# SpeechSynthesisBoard.net
KiCad netlist of a schematic drawn in EAGLE
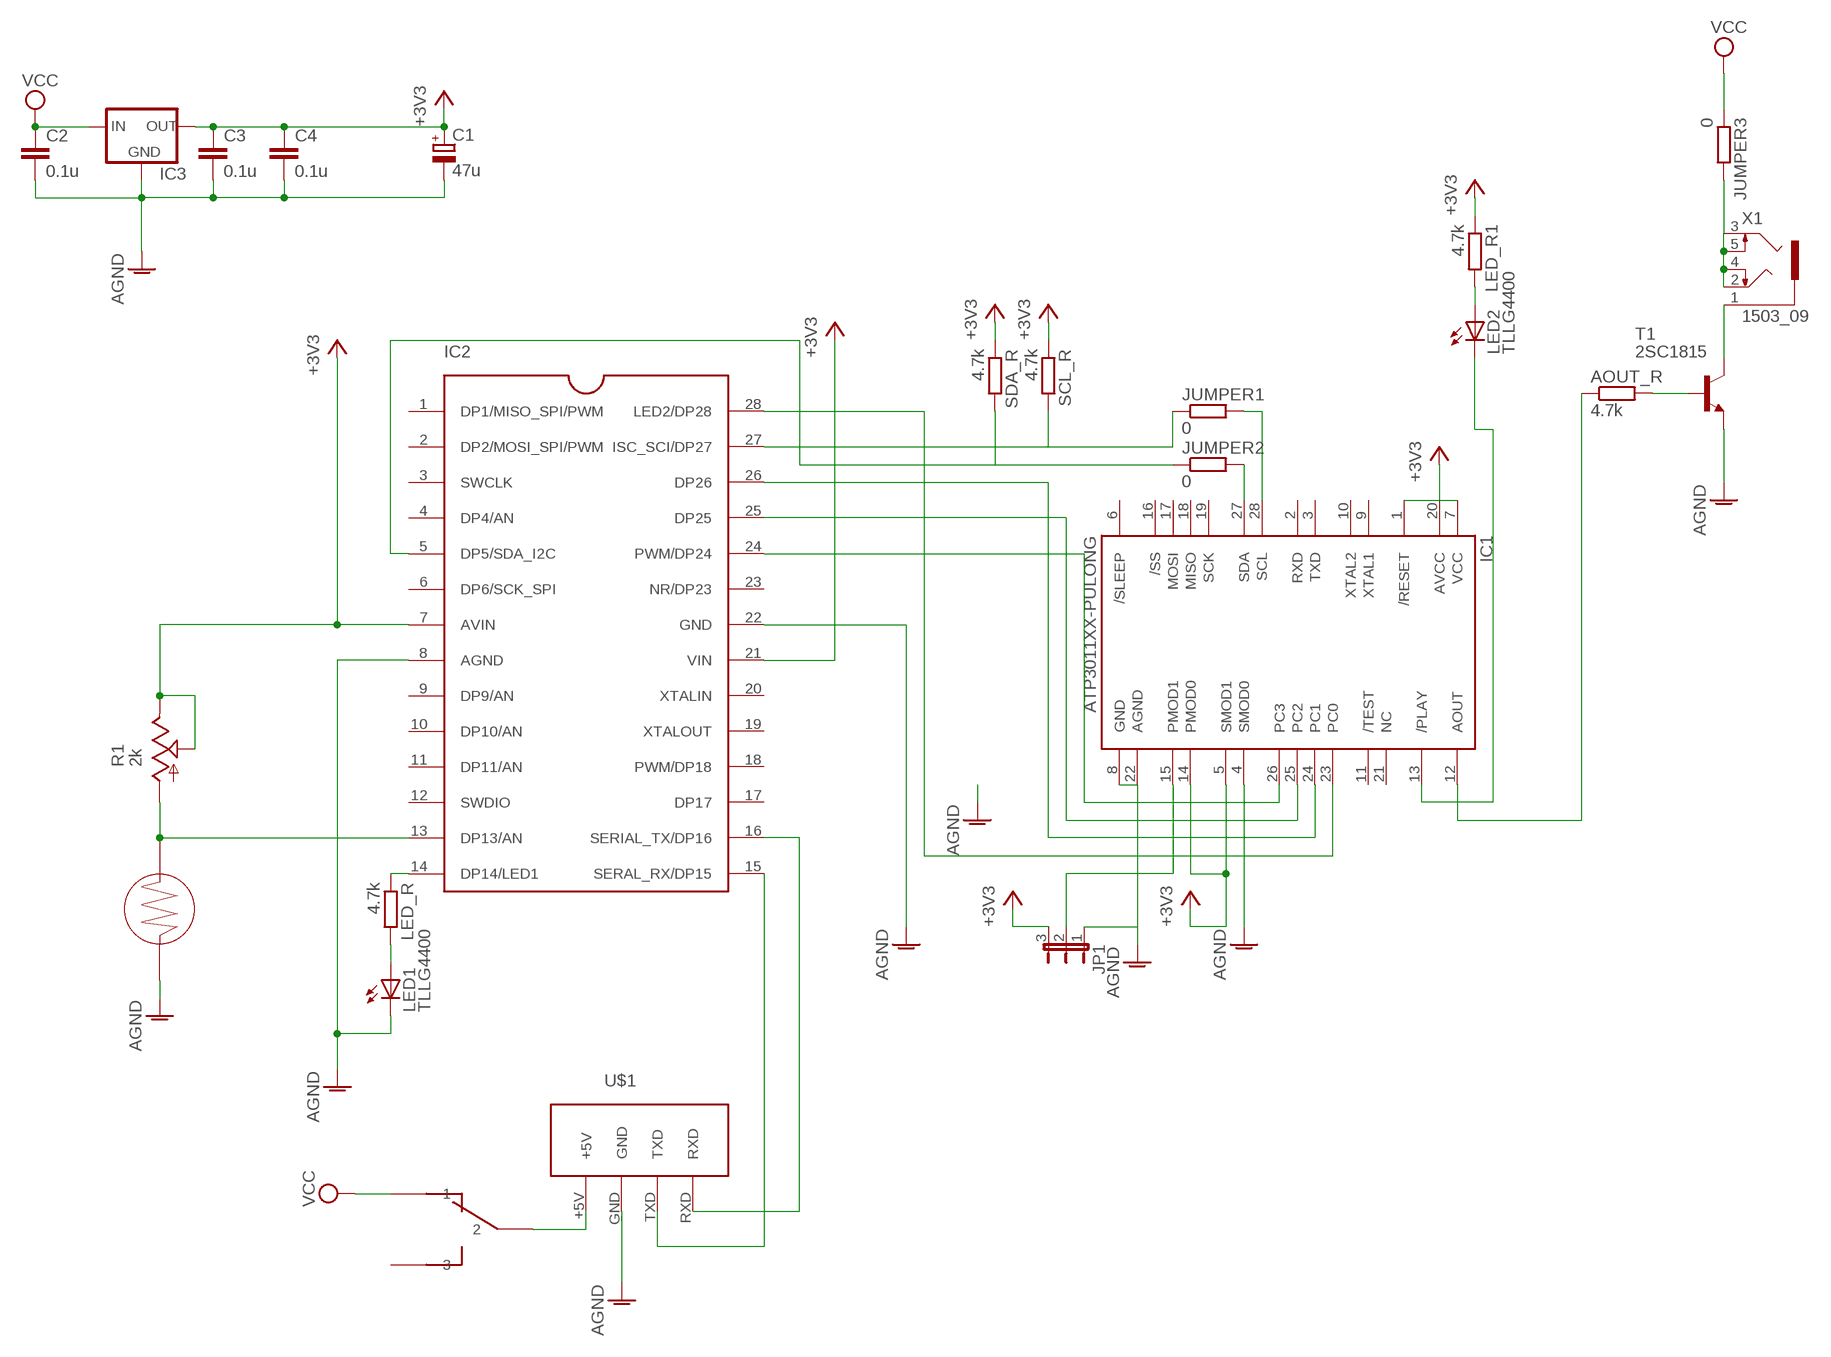
[diagram p0: schematic, sheet 1]

(export (version "E")
  (design (tool "Eeschema 10.0.6"))
  (components
    (comp (ref "AOUT_R")
      (value "4.7k")
      (footprint "eagle-import:0204_7")
      (libsource (lib "eagle-import") (part "R-EU_0204/7"))
    )
    (comp (ref "B-12JB1")
      (value "B-12JV")
      (footprint "eagle-import:B-12JV")
      (libsource (lib "eagle-import") (part "B-12JV"))
    )
    (comp (ref "C1")
      (value "47u")
      (footprint "eagle-import:E2,5-5")
      (libsource (lib "eagle-import") (part "CPOL-EUE2.5-5"))
    )
    (comp (ref "C2")
      (value "0.1u")
      (footprint "eagle-import:C025-024X044")
      (libsource (lib "eagle-import") (part "C-EU025-024X044"))
    )
    (comp (ref "C3")
      (value "0.1u")
      (footprint "eagle-import:C025-024X044")
      (libsource (lib "eagle-import") (part "C-EU025-024X044"))
    )
    (comp (ref "C4")
      (value "0.1u")
      (footprint "eagle-import:C025-024X044")
      (libsource (lib "eagle-import") (part "C-EU025-024X044"))
    )
    (comp (ref "CDS_5MM1")
      (value "CDS_5MM")
      (footprint "eagle-import:CDS_5MM")
      (libsource (lib "eagle-import") (part "CDS_5MM"))
    )
    (comp (ref "IC1")
      (value "ATP3011XX-PULONG")
      (footprint "eagle-import:DIL28-3")
      (libsource (lib "eagle-import") (part "ATP3011XX-PULONG"))
    )
    (comp (ref "IC2")
      (value "LPC1114FN28")
      (footprint "eagle-import:DIP28")
      (libsource (lib "eagle-import") (part "LPC1114FN28"))
    )
    (comp (ref "IC3")
      (value "78XXL")
      (footprint "eagle-import:78XXL")
      (libsource (lib "eagle-import") (part "78XXL"))
    )
    (comp (ref "JP1")
      (value "JP2E")
      (footprint "eagle-import:JP2")
      (libsource (lib "eagle-import") (part "JP2E"))
    )
    (comp (ref "JUMPER1")
      (value "0")
      (footprint "eagle-import:0309_12")
      (libsource (lib "eagle-import") (part "R-EU_0309/12"))
    )
    (comp (ref "JUMPER2")
      (value "0")
      (footprint "eagle-import:0309_12")
      (libsource (lib "eagle-import") (part "R-EU_0309/12"))
    )
    (comp (ref "JUMPER3")
      (value "0")
      (footprint "eagle-import:0309_12")
      (libsource (lib "eagle-import") (part "R-EU_0309/12"))
    )
    (comp (ref "LED1")
      (value "TLLG4400")
      (footprint "eagle-import:LED3MM")
      (fields (field (name "MF") "VISHAY SEMICONDUCTOR"))
      (libsource (lib "eagle-import") (part "TLLG4400"))
    )
    (comp (ref "LED2")
      (value "TLLG4400")
      (footprint "eagle-import:LED3MM")
      (fields (field (name "MF") "VISHAY SEMICONDUCTOR"))
      (libsource (lib "eagle-import") (part "TLLG4400"))
    )
    (comp (ref "LED_R")
      (value "4.7k")
      (footprint "eagle-import:0204_7")
      (libsource (lib "eagle-import") (part "R-EU_0204/7"))
    )
    (comp (ref "LED_R1")
      (value "4.7k")
      (footprint "eagle-import:0204_7")
      (libsource (lib "eagle-import") (part "R-EU_0204/7"))
    )
    (comp (ref "R1")
      (value "2k")
      (footprint "eagle-import:CA6V")
      (libsource (lib "eagle-import") (part "TRIM_US-CA6V"))
    )
    (comp (ref "SCL_R")
      (value "4.7k")
      (footprint "eagle-import:0204_7")
      (libsource (lib "eagle-import") (part "R-EU_0204/7"))
    )
    (comp (ref "SDA_R")
      (value "4.7k")
      (footprint "eagle-import:0204_7")
      (libsource (lib "eagle-import") (part "R-EU_0204/7"))
    )
    (comp (ref "T1")
      (value "2SC1815")
      (footprint "eagle-import:TO92-ECB")
      (libsource (lib "eagle-import") (part "2SC1815"))
    )
    (comp (ref "U$1")
      (value "USB2UART")
      (footprint "eagle-import:USB2UART")
      (libsource (lib "eagle-import") (part "USB2UART"))
    )
    (comp (ref "X1")
      (value "1503_09")
      (footprint "eagle-import:1503_09")
      (libsource (lib "eagle-import") (part "1503_09"))
    )
  )
  (nets
    (net (code "1") (name "+3V3") (class "Default")
      (node (ref "C1") (pin "+") (pinfunction "+_+") (pintype "passive"))
      (node (ref "C3") (pin "1") (pinfunction "1_1") (pintype "passive"))
      (node (ref "C4") (pin "1") (pinfunction "1_1") (pintype "passive"))
      (node (ref "IC1") (pin "1") (pinfunction "/RESET_1") (pintype "input"))
      (node (ref "IC1") (pin "14") (pinfunction "PMOD0_14") (pintype "input"))
      (node (ref "IC1") (pin "20") (pinfunction "AVCC_20") (pintype "power_in"))
      (node (ref "IC1") (pin "5") (pinfunction "SMOD1_5") (pintype "input"))
      (node (ref "IC1") (pin "7") (pinfunction "VCC_7") (pintype "power_in"))
      (node (ref "IC2") (pin "21") (pinfunction "VIN_21") (pintype "power_in"))
      (node (ref "IC2") (pin "7") (pinfunction "AVIN_7") (pintype "power_in"))
      (node (ref "IC3") (pin "OUT") (pinfunction "OUT_OUT") (pintype "passive"))
      (node (ref "JP1") (pin "3") (pinfunction "3_3") (pintype "passive"))
      (node (ref "LED_R1") (pin "1") (pinfunction "1_1") (pintype "passive"))
      (node (ref "R1") (pin "E") (pinfunction "E_E") (pintype "passive"))
      (node (ref "R1") (pin "S") (pinfunction "S_S") (pintype "passive"))
      (node (ref "SCL_R") (pin "1") (pinfunction "1_1") (pintype "passive"))
      (node (ref "SDA_R") (pin "1") (pinfunction "1_1") (pintype "passive"))
    )
    (net (code "2") (name "AGND") (class "Default")
      (node (ref "C1") (pin "-") (pinfunction "-_-") (pintype "passive"))
      (node (ref "C2") (pin "2") (pinfunction "2_2") (pintype "passive"))
      (node (ref "C3") (pin "2") (pinfunction "2_2") (pintype "passive"))
      (node (ref "C4") (pin "2") (pinfunction "2_2") (pintype "passive"))
      (node (ref "CDS_5MM1") (pin "P$2") (pinfunction "P$2_P$2") (pintype "bidirectional"))
      (node (ref "IC1") (pin "22") (pinfunction "AGND_22") (pintype "power_in"))
      (node (ref "IC1") (pin "4") (pinfunction "SMOD0_4") (pintype "input"))
      (node (ref "IC1") (pin "8") (pinfunction "GND_8") (pintype "power_in"))
      (node (ref "IC2") (pin "22") (pinfunction "GND_22") (pintype "power_in"))
      (node (ref "IC2") (pin "8") (pinfunction "AGND_8") (pintype "power_in"))
      (node (ref "IC3") (pin "GND") (pinfunction "GND_GND") (pintype "input"))
      (node (ref "JP1") (pin "1") (pinfunction "1_1") (pintype "passive"))
      (node (ref "LED1") (pin "K") (pinfunction "C_K") (pintype "passive"))
      (node (ref "T1") (pin "E") (pinfunction "E_E") (pintype "passive"))
      (node (ref "U$1") (pin "GND") (pinfunction "GND_GND") (pintype "bidirectional"))
    )
    (net (code "3") (name "Net-(AOUT_R-Pad2)") (class "Default")
      (node (ref "AOUT_R") (pin "2") (pinfunction "2_2") (pintype "passive"))
      (node (ref "T1") (pin "B") (pinfunction "B_B") (pintype "passive"))
    )
    (net (code "4") (name "Net-(B-12JB1-Pad2)") (class "Default")
      (node (ref "B-12JB1") (pin "2") (pinfunction "2_2") (pintype "bidirectional"))
      (node (ref "U$1") (pin "+5V") (pinfunction "+5V_+5V") (pintype "bidirectional"))
    )
    (net (code "5") (name "Net-(IC1-AOUT)") (class "Default")
      (node (ref "AOUT_R") (pin "1") (pinfunction "1_1") (pintype "passive"))
      (node (ref "IC1") (pin "12") (pinfunction "AOUT_12") (pintype "output"))
    )
    (net (code "6") (name "Net-(IC1-PC0)") (class "Default")
      (node (ref "IC1") (pin "23") (pinfunction "PC0_23") (pintype "input"))
      (node (ref "IC2") (pin "28") (pinfunction "LED2/DP28_28") (pintype "bidirectional"))
    )
    (net (code "7") (name "Net-(IC1-PC1)") (class "Default")
      (node (ref "IC1") (pin "24") (pinfunction "PC1_24") (pintype "input"))
      (node (ref "IC2") (pin "26") (pinfunction "DP26_26") (pintype "bidirectional"))
    )
    (net (code "8") (name "Net-(IC1-PC2)") (class "Default")
      (node (ref "IC1") (pin "25") (pinfunction "PC2_25") (pintype "input"))
      (node (ref "IC2") (pin "25") (pinfunction "DP25_25") (pintype "bidirectional"))
    )
    (net (code "9") (name "Net-(IC1-PC3)") (class "Default")
      (node (ref "IC1") (pin "26") (pinfunction "PC3_26") (pintype "input"))
      (node (ref "IC2") (pin "24") (pinfunction "PWM/DP24_24") (pintype "bidirectional"))
    )
    (net (code "10") (name "Net-(IC1-PMOD1)") (class "Default")
      (node (ref "IC1") (pin "15") (pinfunction "PMOD1_15") (pintype "input"))
      (node (ref "JP1") (pin "2") (pinfunction "2_2") (pintype "passive"))
    )
    (net (code "11") (name "Net-(IC1-SCL)") (class "Default")
      (node (ref "IC1") (pin "28") (pinfunction "SCL_28") (pintype "input"))
      (node (ref "JUMPER1") (pin "2") (pinfunction "2_2") (pintype "passive"))
    )
    (net (code "12") (name "Net-(IC1-SDA)") (class "Default")
      (node (ref "IC1") (pin "27") (pinfunction "SDA_27") (pintype "bidirectional"))
      (node (ref "JUMPER2") (pin "2") (pinfunction "2_2") (pintype "passive"))
    )
    (net (code "13") (name "Net-(IC1-{slash}PLAY)") (class "Default")
      (node (ref "IC1") (pin "13") (pinfunction "/PLAY_13") (pintype "output"))
      (node (ref "LED2") (pin "K") (pinfunction "C_K") (pintype "passive"))
    )
    (net (code "14") (name "Net-(IC2-DP5{slash}SDA_I2C)") (class "Default")
      (node (ref "IC2") (pin "5") (pinfunction "DP5/SDA_I2C_5") (pintype "bidirectional"))
      (node (ref "JUMPER2") (pin "1") (pinfunction "1_1") (pintype "passive"))
      (node (ref "SDA_R") (pin "2") (pinfunction "2_2") (pintype "passive"))
    )
    (net (code "15") (name "Net-(IC2-DP13{slash}AN)") (class "Default")
      (node (ref "CDS_5MM1") (pin "P$1") (pinfunction "P$1_P$1") (pintype "bidirectional"))
      (node (ref "IC2") (pin "13") (pinfunction "DP13/AN_13") (pintype "bidirectional"))
      (node (ref "R1") (pin "A") (pinfunction "A_A") (pintype "passive"))
    )
    (net (code "16") (name "Net-(IC2-DP14{slash}LED1)") (class "Default")
      (node (ref "IC2") (pin "14") (pinfunction "DP14/LED1_14") (pintype "bidirectional"))
      (node (ref "LED_R") (pin "1") (pinfunction "1_1") (pintype "passive"))
    )
    (net (code "17") (name "Net-(IC2-ISC_SCI{slash}DP27)") (class "Default")
      (node (ref "IC2") (pin "27") (pinfunction "ISC_SCI/DP27_27") (pintype "bidirectional"))
      (node (ref "JUMPER1") (pin "1") (pinfunction "1_1") (pintype "passive"))
      (node (ref "SCL_R") (pin "2") (pinfunction "2_2") (pintype "passive"))
    )
    (net (code "18") (name "Net-(IC2-SERAL_RX{slash}DP15)") (class "Default")
      (node (ref "IC2") (pin "15") (pinfunction "SERAL_RX/DP15_15") (pintype "bidirectional"))
      (node (ref "U$1") (pin "TXD") (pinfunction "TXD_TXD") (pintype "bidirectional"))
    )
    (net (code "19") (name "Net-(IC2-SERIAL_TX{slash}DP16)") (class "Default")
      (node (ref "IC2") (pin "16") (pinfunction "SERIAL_TX/DP16_16") (pintype "bidirectional"))
      (node (ref "U$1") (pin "RXD") (pinfunction "RXD_RXD") (pintype "bidirectional"))
    )
    (net (code "20") (name "Net-(JUMPER3-Pad2)") (class "Default")
      (node (ref "JUMPER3") (pin "2") (pinfunction "2_2") (pintype "passive"))
      (node (ref "X1") (pin "2") (pinfunction "2_2") (pintype "passive"))
      (node (ref "X1") (pin "3") (pinfunction "3_3") (pintype "passive"))
      (node (ref "X1") (pin "4") (pinfunction "4_4") (pintype "passive"))
      (node (ref "X1") (pin "5") (pinfunction "5_5") (pintype "passive"))
    )
    (net (code "21") (name "Net-(LED1-PadA)") (class "Default")
      (node (ref "LED1") (pin "A") (pinfunction "A_A") (pintype "passive"))
      (node (ref "LED_R") (pin "2") (pinfunction "2_2") (pintype "passive"))
    )
    (net (code "22") (name "Net-(LED2-PadA)") (class "Default")
      (node (ref "LED2") (pin "A") (pinfunction "A_A") (pintype "passive"))
      (node (ref "LED_R1") (pin "2") (pinfunction "2_2") (pintype "passive"))
    )
    (net (code "23") (name "Net-(T1-PadC)") (class "Default")
      (node (ref "T1") (pin "C") (pinfunction "C_C") (pintype "passive"))
      (node (ref "X1") (pin "1") (pinfunction "1_1") (pintype "passive"))
    )
    (net (code "24") (name "VCC") (class "Default")
      (node (ref "B-12JB1") (pin "1") (pinfunction "1_1") (pintype "bidirectional"))
      (node (ref "C2") (pin "1") (pinfunction "1_1") (pintype "passive"))
      (node (ref "IC3") (pin "IN") (pinfunction "IN_IN") (pintype "input"))
      (node (ref "JUMPER3") (pin "1") (pinfunction "1_1") (pintype "passive"))
    )
    (net (code "25") (name "unconnected-(B-12JB1-Pad3)") (class "Default")
      (node (ref "B-12JB1") (pin "3") (pinfunction "3_3") (pintype "bidirectional"))
    )
    (net (code "26") (name "unconnected-(IC1-MISO-Pad18)") (class "Default")
      (node (ref "IC1") (pin "18") (pinfunction "MISO_18") (pintype "output"))
    )
    (net (code "27") (name "unconnected-(IC1-MOSI-Pad17)") (class "Default")
      (node (ref "IC1") (pin "17") (pinfunction "MOSI_17") (pintype "input"))
    )
    (net (code "28") (name "unconnected-(IC1-NC-Pad21)") (class "Default")
      (node (ref "IC1") (pin "21") (pinfunction "NC_21") (pintype "no_connect"))
    )
    (net (code "29") (name "unconnected-(IC1-RXD-Pad2)") (class "Default")
      (node (ref "IC1") (pin "2") (pinfunction "RXD_2") (pintype "input"))
    )
    (net (code "30") (name "unconnected-(IC1-SCK-Pad19)") (class "Default")
      (node (ref "IC1") (pin "19") (pinfunction "SCK_19") (pintype "input"))
    )
    (net (code "31") (name "unconnected-(IC1-TXD-Pad3)") (class "Default")
      (node (ref "IC1") (pin "3") (pinfunction "TXD_3") (pintype "output"))
    )
    (net (code "32") (name "unconnected-(IC1-XTAL1-Pad9)") (class "Default")
      (node (ref "IC1") (pin "9") (pinfunction "XTAL1_9") (pintype "no_connect"))
    )
    (net (code "33") (name "unconnected-(IC1-XTAL2-Pad10)") (class "Default")
      (node (ref "IC1") (pin "10") (pinfunction "XTAL2_10") (pintype "no_connect"))
    )
    (net (code "34") (name "unconnected-(IC1-{slash}SLEEP-Pad6)") (class "Default")
      (node (ref "IC1") (pin "6") (pinfunction "/SLEEP_6") (pintype "input"))
    )
    (net (code "35") (name "unconnected-(IC1-{slash}SS-Pad16)") (class "Default")
      (node (ref "IC1") (pin "16") (pinfunction "/SS_16") (pintype "input"))
    )
    (net (code "36") (name "unconnected-(IC1-{slash}TEST-Pad11)") (class "Default")
      (node (ref "IC1") (pin "11") (pinfunction "/TEST_11") (pintype "input"))
    )
    (net (code "37") (name "unconnected-(IC2-DP1{slash}MISO_SPI{slash}PWM-Pad1)") (class "Default")
      (node (ref "IC2") (pin "1") (pinfunction "DP1/MISO_SPI/PWM_1") (pintype "bidirectional"))
    )
    (net (code "38") (name "unconnected-(IC2-DP2{slash}MOSI_SPI{slash}PWM-Pad2)") (class "Default")
      (node (ref "IC2") (pin "2") (pinfunction "DP2/MOSI_SPI/PWM_2") (pintype "bidirectional"))
    )
    (net (code "39") (name "unconnected-(IC2-DP4{slash}AN-Pad4)") (class "Default")
      (node (ref "IC2") (pin "4") (pinfunction "DP4/AN_4") (pintype "bidirectional"))
    )
    (net (code "40") (name "unconnected-(IC2-DP6{slash}SCK_SPI-Pad6)") (class "Default")
      (node (ref "IC2") (pin "6") (pinfunction "DP6/SCK_SPI_6") (pintype "bidirectional"))
    )
    (net (code "41") (name "unconnected-(IC2-DP9{slash}AN-Pad9)") (class "Default")
      (node (ref "IC2") (pin "9") (pinfunction "DP9/AN_9") (pintype "bidirectional"))
    )
    (net (code "42") (name "unconnected-(IC2-DP10{slash}AN-Pad10)") (class "Default")
      (node (ref "IC2") (pin "10") (pinfunction "DP10/AN_10") (pintype "bidirectional"))
    )
    (net (code "43") (name "unconnected-(IC2-DP11{slash}AN-Pad11)") (class "Default")
      (node (ref "IC2") (pin "11") (pinfunction "DP11/AN_11") (pintype "bidirectional"))
    )
    (net (code "44") (name "unconnected-(IC2-DP17-Pad17)") (class "Default")
      (node (ref "IC2") (pin "17") (pinfunction "DP17_17") (pintype "bidirectional"))
    )
    (net (code "45") (name "unconnected-(IC2-NR{slash}DP23-Pad23)") (class "Default")
      (node (ref "IC2") (pin "23") (pinfunction "NR/DP23_23") (pintype "bidirectional"))
    )
    (net (code "46") (name "unconnected-(IC2-PWM{slash}DP18-Pad18)") (class "Default")
      (node (ref "IC2") (pin "18") (pinfunction "PWM/DP18_18") (pintype "bidirectional"))
    )
    (net (code "47") (name "unconnected-(IC2-SWCLK-Pad3)") (class "Default")
      (node (ref "IC2") (pin "3") (pinfunction "SWCLK_3") (pintype "bidirectional"))
    )
    (net (code "48") (name "unconnected-(IC2-SWDIO-Pad12)") (class "Default")
      (node (ref "IC2") (pin "12") (pinfunction "SWDIO_12") (pintype "bidirectional"))
    )
    (net (code "49") (name "unconnected-(IC2-XTALIN-Pad20)") (class "Default")
      (node (ref "IC2") (pin "20") (pinfunction "XTALIN_20") (pintype "input"))
    )
    (net (code "50") (name "unconnected-(IC2-XTALOUT-Pad19)") (class "Default")
      (node (ref "IC2") (pin "19") (pinfunction "XTALOUT_19") (pintype "output"))
    )
  )
)
